# MAIN_MCU_CT2650.net
KiCad netlist of a schematic drawn in Altium Designer
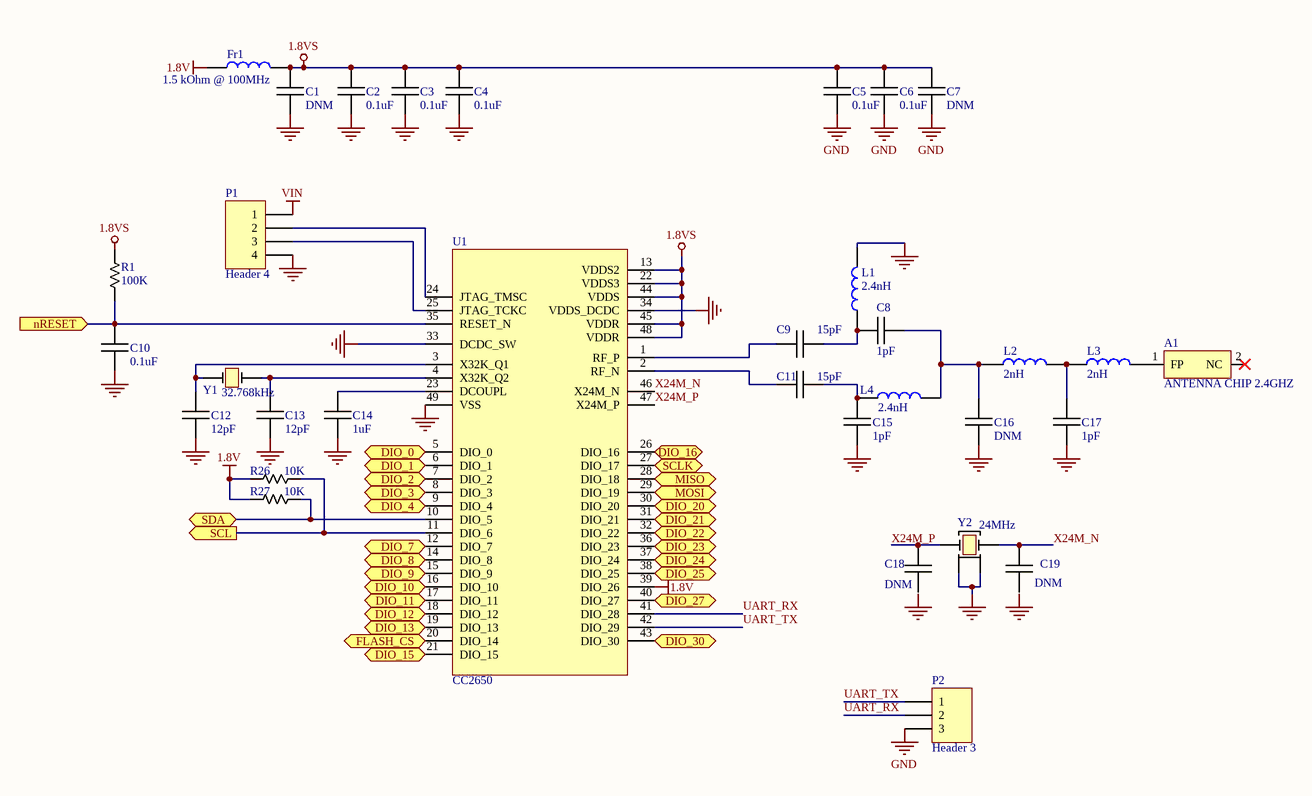
[diagram p0: MAIN_MCU_CT2650.SchDoc]

(export (version "E")
  (design (tool "Eeschema 10.0.6"))
  (components
    (comp (ref "A1")
      (value "ANTENNA CHIP 2.4GHZ")
      (fields (field (name "DIGI-KEY PART NUMBER") "712-1006-1-ND"))
      (libsource (lib "HR_lib") (part "ANTENNA CHIP 2.4GHZ"))
    )
    (comp (ref "C1") (value "DNM") (description "SMD_CAPACITOR") (libsource (lib "test") (part "DNM")))
    (comp (ref "C2")
      (value "0.1uF")
      (description "SMD_CAPACITOR")
      (fields (field (name "DIGI-KEY PART NUMBER") "490-6319-1-ND") (field (name "TOLERANCE") "±10%"))
      (libsource (lib "test") (part "C0.1uF_0402"))
    )
    (comp (ref "C3")
      (value "0.1uF")
      (description "SMD_CAPACITOR")
      (fields (field (name "DIGI-KEY PART NUMBER") "490-6319-1-ND") (field (name "TOLERANCE") "±10%"))
      (libsource (lib "test") (part "C0.1uF_0402"))
    )
    (comp (ref "C4")
      (value "0.1uF")
      (description "SMD_CAPACITOR")
      (fields (field (name "DIGI-KEY PART NUMBER") "490-6319-1-ND") (field (name "TOLERANCE") "±10%"))
      (libsource (lib "test") (part "C0.1uF_0402"))
    )
    (comp (ref "C5")
      (value "0.1uF")
      (description "SMD_CAPACITOR")
      (fields (field (name "DIGI-KEY PART NUMBER") "490-6319-1-ND") (field (name "TOLERANCE") "±10%"))
      (libsource (lib "test") (part "C0.1uF_0402"))
    )
    (comp (ref "C6")
      (value "0.1uF")
      (description "SMD_CAPACITOR")
      (fields (field (name "DIGI-KEY PART NUMBER") "490-6319-1-ND") (field (name "TOLERANCE") "±10%"))
      (libsource (lib "test") (part "C0.1uF_0402"))
    )
    (comp (ref "C7") (value "DNM") (description "SMD_CAPACITOR") (libsource (lib "test") (part "DNM")))
    (comp (ref "C8")
      (value "1pF")
      (description "SMD_CAPACITOR")
      (fields (field (name "DIGI-KEY PART NUMBER") "490-3199-1-ND") (field (name "TOLERANCE") "±0.25pF"))
      (libsource (lib "test") (part "C1pF_0402"))
    )
    (comp (ref "C9")
      (value "15pF")
      (description "SMD_CAPACITOR")
      (fields (field (name "DIGI-KEY PART NUMBER") "712-1261-1-ND") (field (name "TOLERANCE") "±5%"))
      (libsource (lib "Schlib1") (part "C15pF_0603"))
    )
    (comp (ref "C10")
      (value "0.1uF")
      (description "SMD_CAPACITOR")
      (fields (field (name "DIGI-KEY PART NUMBER") "490-6319-1-ND") (field (name "TOLERANCE") "±10%"))
      (libsource (lib "test") (part "C0.1uF_0402"))
    )
    (comp (ref "C11")
      (value "15pF")
      (description "SMD_CAPACITOR")
      (fields (field (name "DIGI-KEY PART NUMBER") "712-1261-1-ND") (field (name "TOLERANCE") "±5%"))
      (libsource (lib "Schlib1") (part "C15pF_0603"))
    )
    (comp (ref "C12")
      (value "12pF")
      (description "SMD_CAPACITOR")
      (fields (field (name "DIGI-KEY PART NUMBER") "490-5924-1-ND") (field (name "TOLERANCE") "±5%"))
      (libsource (lib "test") (part "C12pF_0402"))
    )
    (comp (ref "C13")
      (value "12pF")
      (description "SMD_CAPACITOR")
      (fields (field (name "DIGI-KEY PART NUMBER") "490-5924-1-ND") (field (name "TOLERANCE") "±5%"))
      (libsource (lib "test") (part "C12pF_0402"))
    )
    (comp (ref "C14")
      (value "1uF")
      (description "SMD_CAPACITOR")
      (fields (field (name "DIGI-KEY PART NUMBER") "490-3890-1-ND") (field (name "TOLERANCE") "±10%"))
      (libsource (lib "test") (part "C1uF_0402"))
    )
    (comp (ref "C15")
      (value "1pF")
      (description "SMD_CAPACITOR")
      (fields (field (name "DIGI-KEY PART NUMBER") "490-3199-1-ND") (field (name "TOLERANCE") "±0.25pF"))
      (libsource (lib "test") (part "C1pF_0402"))
    )
    (comp (ref "C16") (value "DNM") (description "SMD_CAPACITOR") (libsource (lib "test") (part "DNM")))
    (comp (ref "C17")
      (value "1pF")
      (description "SMD_CAPACITOR")
      (fields (field (name "DIGI-KEY PART NUMBER") "490-3199-1-ND") (field (name "TOLERANCE") "±0.25pF"))
      (libsource (lib "test") (part "C1pF_0402"))
    )
    (comp (ref "C18") (value "DNM") (description "SMD_CAPACITOR") (libsource (lib "test") (part "DNM")))
    (comp (ref "C19") (value "DNM") (description "SMD_CAPACITOR") (libsource (lib "test") (part "DNM")))
    (comp (ref "Fr1")
      (value "1.5 kOhm @ 100MHz")
      (description "SMD_Ferrite Beads")
      (fields (field (name "DIGI-KEY PART NUMBER") "490-5216-1-ND"))
      (libsource (lib "test") (part "Fr1.5 kOhm"))
    )
    (comp (ref "L1")
      (value "2.4nH")
      (description "SMD_Inductor")
      (fields (field (name "DIGI-KEY PART NUMBER") "490-8389-1-ND"))
      (libsource (lib "test") (part "L2.4nH_0402"))
    )
    (comp (ref "L2")
      (value "2nH")
      (description "SMD_Inductor")
      (fields (field (name "DIGI-KEY PART NUMBER") "490-6569-1-ND"))
      (libsource (lib "test") (part "L2nH_0402"))
    )
    (comp (ref "L3")
      (value "2nH")
      (description "SMD_Inductor")
      (fields (field (name "DIGI-KEY PART NUMBER") "490-6569-1-ND"))
      (libsource (lib "test") (part "L2nH_0402"))
    )
    (comp (ref "L4")
      (value "2.4nH")
      (description "SMD_Inductor")
      (fields (field (name "DIGI-KEY PART NUMBER") "490-8389-1-ND"))
      (libsource (lib "test") (part "L2.4nH_0402"))
    )
    (comp (ref "P1")
      (value "Header 4")
      (footprint "HDR1X4")
      (description "Header, 4-Pin")
      (fields (field (name "PUBLISHER") "Altium Limited"))
      (libsource (lib "Miscellaneous Connectors") (part "Header 4"))
    )
    (comp (ref "P2")
      (value "Header 3")
      (footprint "HDR1X3")
      (description "Header, 3-Pin")
      (fields (field (name "PUBLISHER") "Altium Limited"))
      (libsource (lib "Miscellaneous Connectors") (part "Header 3"))
    )
    (comp (ref "R1")
      (value "100K")
      (footprint "R0603")
      (description "SMD_RESISTOR")
      (fields (field (name "DIGI-KEY PART NUMBER") "541-2190-1-ND") (field (name "TOLERANCE") "±5%"))
      (libsource (lib "test") (part "R100K_0402"))
    )
    (comp (ref "R26")
      (value "10K")
      (footprint "0603:R0603")
      (description "SMD_RESISTOR")
      (fields (field (name "DIGI-KEY PART NUMBER") "311-10KNCT-ND") (field (name "TOLERANCE") "±5%"))
      (libsource (lib "HR_lib") (part "R10K_0201"))
    )
    (comp (ref "R27")
      (value "10K")
      (footprint "0603:R0603")
      (description "SMD_RESISTOR")
      (fields (field (name "DIGI-KEY PART NUMBER") "311-10KNCT-ND") (field (name "TOLERANCE") "±5%"))
      (libsource (lib "HR_lib") (part "R10K_0201"))
    )
    (comp (ref "U1")
      (value "CC2650")
      (description "IC RF TXRX+MCU 802.15.4/BT 48QFN")
      (fields (field (name "DIGI-KEY PART NUMBER") "296-44316-1-ND"))
      (libsource (lib "Schlib1") (part "CC2650F128RGZR"))
    )
    (comp (ref "Y1")
      (value "32.768kHz")
      (description "Crystal")
      (fields (field (name "DIGI-KEY PART NUMBER") "SER4077CT-ND"))
      (libsource (lib "test") (part "32.7680KHz_SMD"))
    )
    (comp (ref "Y2")
      (value "24MHz")
      (description "Crystal")
      (fields (field (name "DIGI-KEY PART NUMBER") "SER3635CT-ND"))
      (libsource (lib "HR_lib") (part "24MHz_SMD"))
    )
  )
  (nets
    (net (code "1") (name "/DIO_0") (class "Default")
      (node (ref "U1") (pin "5") (pinfunction "DIO_0_5") (pintype "passive"))
    )
    (net (code "2") (name "/DIO_1") (class "Default")
      (node (ref "U1") (pin "6") (pinfunction "DIO_1_6") (pintype "passive"))
    )
    (net (code "3") (name "/DIO_2") (class "Default")
      (node (ref "U1") (pin "7") (pinfunction "DIO_2_7") (pintype "passive"))
    )
    (net (code "4") (name "/DIO_3") (class "Default")
      (node (ref "U1") (pin "8") (pinfunction "DIO_3_8") (pintype "passive"))
    )
    (net (code "5") (name "/DIO_4") (class "Default")
      (node (ref "U1") (pin "9") (pinfunction "DIO_4_9") (pintype "passive"))
    )
    (net (code "6") (name "/DIO_7") (class "Default")
      (node (ref "U1") (pin "12") (pinfunction "DIO_7_12") (pintype "passive"))
    )
    (net (code "7") (name "/DIO_8") (class "Default")
      (node (ref "U1") (pin "14") (pinfunction "DIO_8_14") (pintype "passive"))
    )
    (net (code "8") (name "/DIO_9") (class "Default")
      (node (ref "U1") (pin "15") (pinfunction "DIO_9_15") (pintype "passive"))
    )
    (net (code "9") (name "/DIO_10") (class "Default")
      (node (ref "U1") (pin "16") (pinfunction "DIO_10_16") (pintype "passive"))
    )
    (net (code "10") (name "/DIO_11") (class "Default")
      (node (ref "U1") (pin "17") (pinfunction "DIO_11_17") (pintype "passive"))
    )
    (net (code "11") (name "/DIO_12") (class "Default")
      (node (ref "U1") (pin "18") (pinfunction "DIO_12_18") (pintype "passive"))
    )
    (net (code "12") (name "/DIO_13") (class "Default")
      (node (ref "U1") (pin "19") (pinfunction "DIO_13_19") (pintype "passive"))
    )
    (net (code "13") (name "/DIO_15") (class "Default")
      (node (ref "U1") (pin "21") (pinfunction "DIO_15_21") (pintype "passive"))
    )
    (net (code "14") (name "/DIO_16") (class "Default")
      (node (ref "U1") (pin "26") (pinfunction "DIO_16_26") (pintype "passive"))
    )
    (net (code "15") (name "/DIO_20") (class "Default")
      (node (ref "U1") (pin "30") (pinfunction "DIO_20_30") (pintype "passive"))
    )
    (net (code "16") (name "/DIO_21") (class "Default")
      (node (ref "U1") (pin "31") (pinfunction "DIO_21_31") (pintype "passive"))
    )
    (net (code "17") (name "/DIO_22") (class "Default")
      (node (ref "U1") (pin "32") (pinfunction "DIO_22_32") (pintype "passive"))
    )
    (net (code "18") (name "/DIO_23") (class "Default")
      (node (ref "U1") (pin "36") (pinfunction "DIO_23_36") (pintype "passive"))
    )
    (net (code "19") (name "/DIO_24") (class "Default")
      (node (ref "U1") (pin "37") (pinfunction "DIO_24_37") (pintype "passive"))
    )
    (net (code "20") (name "/DIO_25") (class "Default")
      (node (ref "U1") (pin "38") (pinfunction "DIO_25_38") (pintype "passive"))
    )
    (net (code "21") (name "/DIO_27") (class "Default")
      (node (ref "U1") (pin "40") (pinfunction "DIO_27_40") (pintype "passive"))
    )
    (net (code "22") (name "/DIO_30") (class "Default")
      (node (ref "U1") (pin "43") (pinfunction "DIO_30_43") (pintype "passive"))
    )
    (net (code "23") (name "/FLASH_CS") (class "Default")
      (node (ref "U1") (pin "20") (pinfunction "DIO_14_20") (pintype "passive"))
    )
    (net (code "24") (name "/MISO") (class "Default")
      (node (ref "U1") (pin "28") (pinfunction "DIO_18_28") (pintype "passive"))
    )
    (net (code "25") (name "/MOSI") (class "Default")
      (node (ref "U1") (pin "29") (pinfunction "DIO_19_29") (pintype "passive"))
    )
    (net (code "26") (name "/SCL") (class "Default")
      (node (ref "R26") (pin "2") (pintype "passive"))
      (node (ref "U1") (pin "11") (pinfunction "DIO_6_11") (pintype "passive"))
    )
    (net (code "27") (name "/SCLK") (class "Default")
      (node (ref "U1") (pin "27") (pinfunction "DIO_17_27") (pintype "passive"))
    )
    (net (code "28") (name "/SDA") (class "Default")
      (node (ref "R27") (pin "2") (pintype "passive"))
      (node (ref "U1") (pin "10") (pinfunction "DIO_5_10") (pintype "passive"))
    )
    (net (code "29") (name "/UART_RX") (class "Default")
      (node (ref "P2") (pin "2") (pinfunction "2_2") (pintype "passive"))
      (node (ref "U1") (pin "41") (pinfunction "DIO_28_41") (pintype "passive"))
    )
    (net (code "30") (name "/UART_TX") (class "Default")
      (node (ref "P2") (pin "1") (pinfunction "1_1") (pintype "passive"))
      (node (ref "U1") (pin "42") (pinfunction "DIO_29_42") (pintype "passive"))
    )
    (net (code "31") (name "/X24M_N") (class "Default")
      (node (ref "U1") (pin "46") (pinfunction "X24M_N_46") (pintype "passive"))
    )
    (net (code "32") (name "/X24M_P") (class "Default")
      (node (ref "U1") (pin "47") (pinfunction "X24M_P_47") (pintype "passive"))
    )
    (net (code "33") (name "/nRESET") (class "Default")
      (node (ref "C10") (pin "2") (pintype "passive"))
      (node (ref "R1") (pin "1") (pintype "passive"))
      (node (ref "U1") (pin "35") (pinfunction "RESET_N_35") (pintype "passive"))
    )
    (net (code "34") (name "1.8V") (class "Default")
      (node (ref "Fr1") (pin "1") (pinfunction "1_1") (pintype "passive"))
      (node (ref "R26") (pin "1") (pintype "passive"))
      (node (ref "R27") (pin "1") (pintype "passive"))
      (node (ref "U1") (pin "39") (pinfunction "DIO_26_39") (pintype "passive"))
    )
    (net (code "35") (name "1.8VS") (class "Default")
      (node (ref "C1") (pin "2") (pintype "passive"))
      (node (ref "C2") (pin "2") (pintype "passive"))
      (node (ref "C3") (pin "2") (pintype "passive"))
      (node (ref "C4") (pin "2") (pintype "passive"))
      (node (ref "C5") (pin "2") (pintype "passive"))
      (node (ref "C6") (pin "2") (pintype "passive"))
      (node (ref "C7") (pin "2") (pintype "passive"))
      (node (ref "Fr1") (pin "2") (pinfunction "2_2") (pintype "passive"))
      (node (ref "R1") (pin "2") (pintype "passive"))
      (node (ref "U1") (pin "13") (pinfunction "VDDS2_13") (pintype "passive"))
      (node (ref "U1") (pin "22") (pinfunction "VDDS3_22") (pintype "passive"))
      (node (ref "U1") (pin "44") (pinfunction "VDDS_44") (pintype "passive"))
      (node (ref "U1") (pin "45") (pinfunction "VDDR_45") (pintype "passive"))
      (node (ref "U1") (pin "48") (pinfunction "VDDR_48") (pintype "passive"))
    )
    (net (code "36") (name "GND") (class "Default")
      (node (ref "C1") (pin "1") (pintype "passive"))
      (node (ref "C10") (pin "1") (pintype "passive"))
      (node (ref "C12") (pin "1") (pintype "passive"))
      (node (ref "C13") (pin "1") (pintype "passive"))
      (node (ref "C14") (pin "1") (pintype "passive"))
      (node (ref "C15") (pin "1") (pintype "passive"))
      (node (ref "C16") (pin "1") (pintype "passive"))
      (node (ref "C17") (pin "1") (pintype "passive"))
      (node (ref "C2") (pin "1") (pintype "passive"))
      (node (ref "C3") (pin "1") (pintype "passive"))
      (node (ref "C4") (pin "1") (pintype "passive"))
      (node (ref "C5") (pin "1") (pintype "passive"))
      (node (ref "C6") (pin "1") (pintype "passive"))
      (node (ref "C7") (pin "1") (pintype "passive"))
      (node (ref "L1") (pin "2") (pinfunction "2_2") (pintype "passive"))
      (node (ref "P1") (pin "4") (pinfunction "4_4") (pintype "passive"))
      (node (ref "P2") (pin "3") (pinfunction "3_3") (pintype "passive"))
      (node (ref "U1") (pin "33") (pinfunction "DCDC_SW_33") (pintype "passive"))
      (node (ref "U1") (pin "34") (pinfunction "VDDS_DCDC_34") (pintype "passive"))
      (node (ref "U1") (pin "49") (pinfunction "VSS_49") (pintype "passive"))
      (node (ref "Y2") (pin "2") (pinfunction "2_2") (pintype "passive"))
      (node (ref "Y2") (pin "4") (pinfunction "4_4") (pintype "passive"))
    )
    (net (code "37") (name "Net-(A1-FP)") (class "Default")
      (node (ref "A1") (pin "1") (pinfunction "FP_1") (pintype "passive"))
      (node (ref "L3") (pin "2") (pinfunction "2_2") (pintype "passive"))
    )
    (net (code "38") (name "Net-(C8-Pad1)") (class "Default")
      (node (ref "C8") (pin "1") (pintype "passive"))
      (node (ref "C9") (pin "2") (pintype "passive"))
      (node (ref "L1") (pin "1") (pinfunction "1_1") (pintype "passive"))
    )
    (net (code "39") (name "Net-(C11-Pad2)") (class "Default")
      (node (ref "C11") (pin "2") (pintype "passive"))
      (node (ref "C15") (pin "2") (pintype "passive"))
      (node (ref "L4") (pin "1") (pinfunction "1_1") (pintype "passive"))
    )
    (net (code "40") (name "Net-(C16-Pad2)") (class "Default")
      (node (ref "C16") (pin "2") (pintype "passive"))
      (node (ref "C8") (pin "2") (pintype "passive"))
      (node (ref "L2") (pin "1") (pinfunction "1_1") (pintype "passive"))
      (node (ref "L4") (pin "2") (pinfunction "2_2") (pintype "passive"))
    )
    (net (code "41") (name "Net-(C17-Pad2)") (class "Default")
      (node (ref "C17") (pin "2") (pintype "passive"))
      (node (ref "L2") (pin "2") (pinfunction "2_2") (pintype "passive"))
      (node (ref "L3") (pin "1") (pinfunction "1_1") (pintype "passive"))
    )
    (net (code "42") (name "Net-(C18-Pad2)") (class "Default")
      (node (ref "C18") (pin "2") (pintype "passive"))
      (node (ref "Y2") (pin "1") (pinfunction "1_1") (pintype "passive"))
    )
    (net (code "43") (name "Net-(C19-Pad2)") (class "Default")
      (node (ref "C19") (pin "2") (pintype "passive"))
      (node (ref "Y2") (pin "3") (pinfunction "3_3") (pintype "passive"))
    )
    (net (code "44") (name "Net-(U1-DCOUPL)") (class "Default")
      (node (ref "C14") (pin "2") (pintype "passive"))
      (node (ref "U1") (pin "23") (pinfunction "DCOUPL_23") (pintype "passive"))
    )
    (net (code "45") (name "Net-(U1-JTAG_TCKC)") (class "Default")
      (node (ref "P1") (pin "3") (pinfunction "3_3") (pintype "passive"))
      (node (ref "U1") (pin "25") (pinfunction "JTAG_TCKC_25") (pintype "passive"))
    )
    (net (code "46") (name "Net-(U1-JTAG_TMSC)") (class "Default")
      (node (ref "P1") (pin "2") (pinfunction "2_2") (pintype "passive"))
      (node (ref "U1") (pin "24") (pinfunction "JTAG_TMSC_24") (pintype "passive"))
    )
    (net (code "47") (name "Net-(U1-RF_N)") (class "Default")
      (node (ref "C11") (pin "1") (pintype "passive"))
      (node (ref "U1") (pin "2") (pinfunction "RF_N_2") (pintype "passive"))
    )
    (net (code "48") (name "Net-(U1-RF_P)") (class "Default")
      (node (ref "C9") (pin "1") (pintype "passive"))
      (node (ref "U1") (pin "1") (pinfunction "RF_P_1") (pintype "passive"))
    )
    (net (code "49") (name "Net-(U1-X32K_Q1)") (class "Default")
      (node (ref "C12") (pin "2") (pintype "passive"))
      (node (ref "U1") (pin "3") (pinfunction "X32K_Q1_3") (pintype "passive"))
      (node (ref "Y1") (pin "1") (pinfunction "1_1") (pintype "passive"))
    )
    (net (code "50") (name "Net-(U1-X32K_Q2)") (class "Default")
      (node (ref "C13") (pin "2") (pintype "passive"))
      (node (ref "U1") (pin "4") (pinfunction "X32K_Q2_4") (pintype "passive"))
      (node (ref "Y1") (pin "2") (pinfunction "2_2") (pintype "passive"))
    )
    (net (code "51") (name "VIN") (class "Default")
      (node (ref "P1") (pin "1") (pinfunction "1_1") (pintype "passive"))
    )
    (net (code "52") (name "unconnected-(A1-NC-Pad2)") (class "Default")
      (node (ref "A1") (pin "2") (pinfunction "NC_2") (pintype "passive+no_connect"))
    )
    (net (code "53") (name "unconnected-(C18-Pad1)") (class "Default")
      (node (ref "C18") (pin "1") (pintype "passive"))
    )
    (net (code "54") (name "unconnected-(C19-Pad1)") (class "Default")
      (node (ref "C19") (pin "1") (pintype "passive"))
    )
  )
)
